# Option_key.net
KiCad netlist of a schematic drawn in Altium Designer
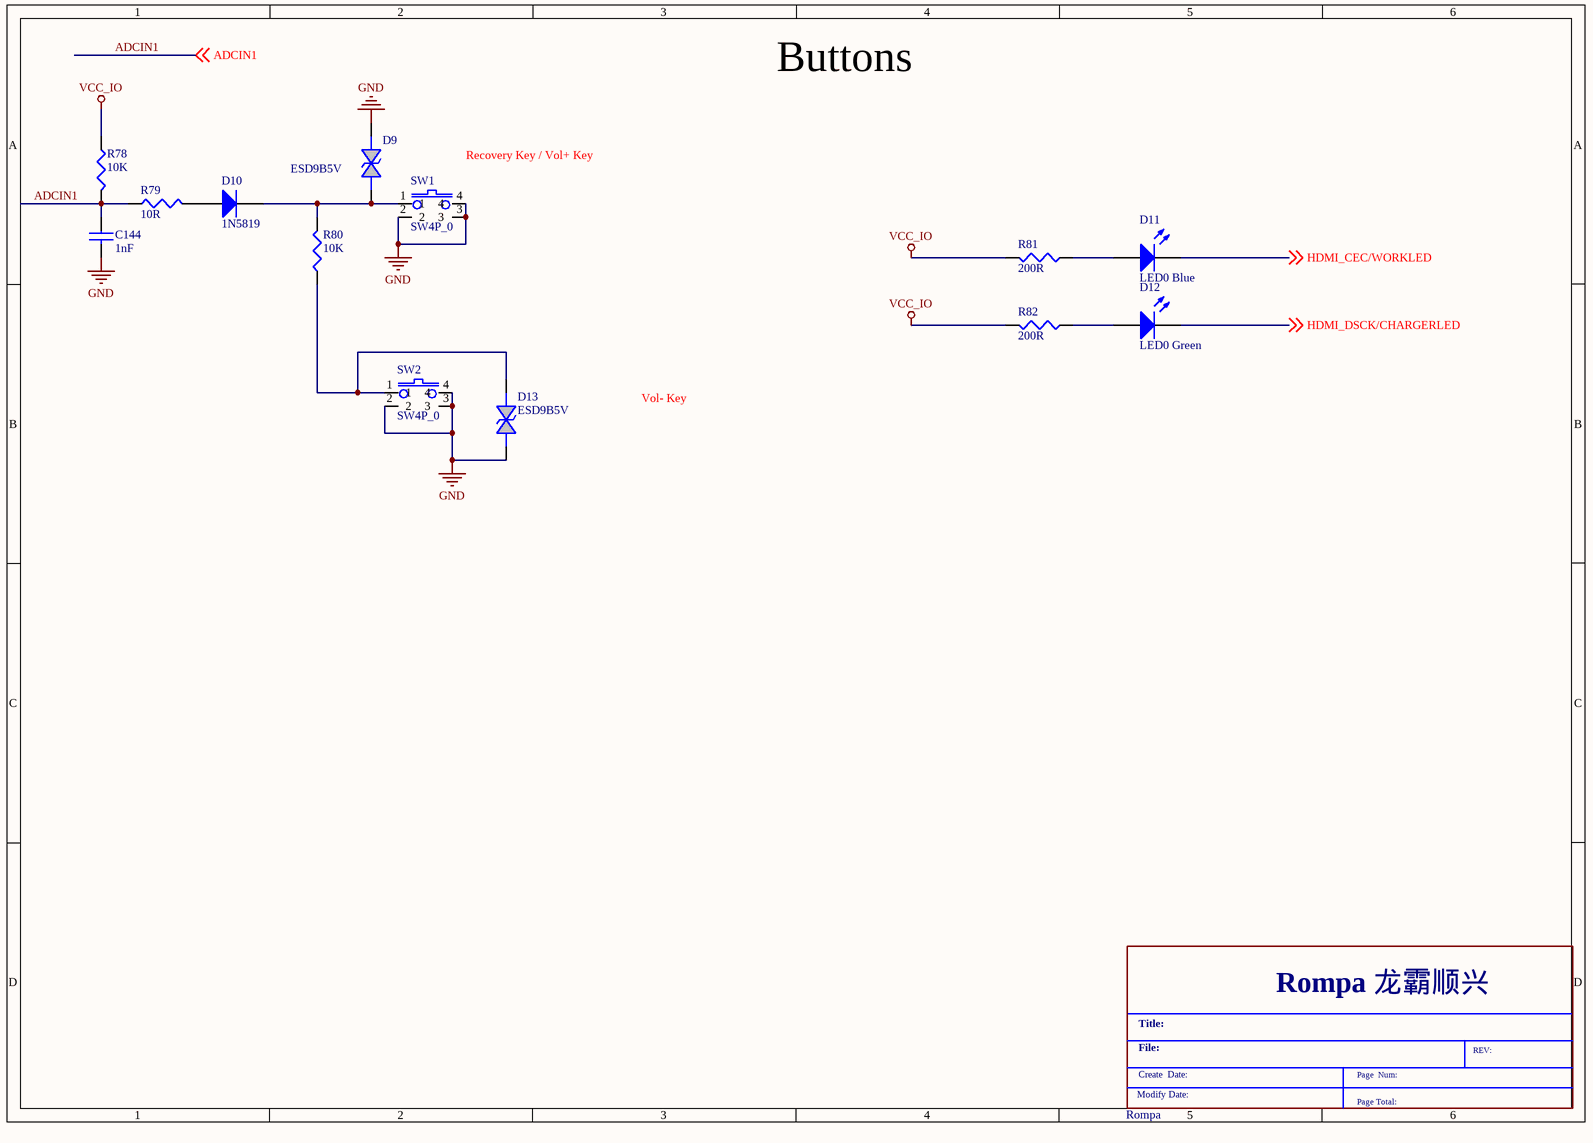
[diagram p0: Option_key.SchDoc]

(export (version "E")
  (design (tool "Eeschema 10.0.6"))
  (components
    (comp (ref "C144")
      (value "1nF")
      (footprint "C0402")
      (description "16V")
      (libsource (lib "RK3128_BETA_V03_20151231_Library") (part "CAP NP"))
    )
    (comp (ref "D9")
      (value "ESD9B5V")
      (description "FP:E0402N")
      (libsource (lib "RK3128_BETA_V03_20151231_Library") (part "DIODE BI-DIR TRIG"))
    )
    (comp (ref "D10")
      (value "1N5819")
      (fields (field (name "PUBLISHER") "Altium Limited"))
      (libsource (lib "Miscellaneous Devices") (part "Diode"))
    )
    (comp (ref "D11")
      (value "LED0 Blue")
      (footprint "1608[0603]")
      (description "Typical INFRARED GaAs LED   Blue")
      (fields (field (name "PUBLISHER") "Altium Limited"))
      (libsource (lib "Miscellaneous Devices") (part "LED0"))
    )
    (comp (ref "D12")
      (value "LED0 Green")
      (footprint "1608[0603]")
      (description "Typical INFRARED GaAs LED   Blue")
      (fields (field (name "PUBLISHER") "Altium Limited"))
      (libsource (lib "Miscellaneous Devices") (part "LED0"))
    )
    (comp (ref "D13")
      (value "ESD9B5V")
      (description "FP:E0402N")
      (libsource (lib "RK3128_BETA_V03_20151231_Library") (part "DIODE BI-DIR TRIG"))
    )
    (comp (ref "R78")
      (value "10K")
      (footprint "R0402")
      (description "%1")
      (libsource (lib "RK3128_BETA_V03_20151231_Library") (part "RESISTOR"))
    )
    (comp (ref "R79")
      (value "10R")
      (footprint "R0402")
      (libsource (lib "RK3128_BETA_V03_20151231_Library") (part "RESISTOR"))
    )
    (comp (ref "R80")
      (value "10K")
      (footprint "R0402")
      (libsource (lib "RK3128_BETA_V03_20151231_Library") (part "RESISTOR"))
    )
    (comp (ref "R81")
      (value "200R")
      (footprint "R0402")
      (libsource (lib "RK3128_BETA_V03_20151231_Library") (part "RESISTOR"))
    )
    (comp (ref "R82")
      (value "200R")
      (footprint "R0402")
      (libsource (lib "RK3128_BETA_V03_20151231_Library") (part "RESISTOR"))
    )
    (comp (ref "SW1") (value "SW4P_0") (libsource (lib "RK3128_BETA_V03_20151231_Library") (part "SW4P_0")))
    (comp (ref "SW2") (value "SW4P_0") (libsource (lib "RK3128_BETA_V03_20151231_Library") (part "SW4P_0")))
  )
  (nets
    (net (code "1") (name "ADCIN1") (class "Default")
      (node (ref "C144") (pin "1") (pinfunction "1_1") (pintype "passive"))
      (node (ref "R78") (pin "2") (pinfunction "2_2") (pintype "passive"))
      (node (ref "R79") (pin "1") (pinfunction "1_1") (pintype "passive"))
    )
    (net (code "2") (name "GND") (class "Default")
      (node (ref "C144") (pin "2") (pinfunction "2_2") (pintype "passive"))
      (node (ref "D13") (pin "2") (pinfunction "2_2") (pintype "passive"))
      (node (ref "D9") (pin "2") (pinfunction "2_2") (pintype "passive"))
      (node (ref "SW1") (pin "2") (pinfunction "2_2") (pintype "passive"))
      (node (ref "SW1") (pin "3") (pinfunction "3_3") (pintype "passive"))
      (node (ref "SW1") (pin "4") (pinfunction "4_4") (pintype "passive"))
      (node (ref "SW2") (pin "2") (pinfunction "2_2") (pintype "passive"))
      (node (ref "SW2") (pin "3") (pinfunction "3_3") (pintype "passive"))
      (node (ref "SW2") (pin "4") (pinfunction "4_4") (pintype "passive"))
    )
    (net (code "3") (name "HDMI_CEC{slash}WORKLED") (class "Default")
      (node (ref "D11") (pin "2") (pinfunction "K_2") (pintype "passive"))
    )
    (net (code "4") (name "HDMI_DSCK{slash}CHARGERLED") (class "Default")
      (node (ref "D12") (pin "2") (pinfunction "K_2") (pintype "passive"))
    )
    (net (code "5") (name "Net-(D10-A)") (class "Default")
      (node (ref "D10") (pin "1") (pinfunction "A_1") (pintype "passive"))
      (node (ref "R79") (pin "2") (pinfunction "2_2") (pintype "passive"))
    )
    (net (code "6") (name "Net-(D10-K)") (class "Default")
      (node (ref "D10") (pin "2") (pinfunction "K_2") (pintype "passive"))
      (node (ref "D9") (pin "1") (pinfunction "1_1") (pintype "passive"))
      (node (ref "R80") (pin "2") (pinfunction "2_2") (pintype "passive"))
      (node (ref "SW1") (pin "1") (pinfunction "1_1") (pintype "passive"))
    )
    (net (code "7") (name "Net-(D11-A)") (class "Default")
      (node (ref "D11") (pin "1") (pinfunction "A_1") (pintype "passive"))
      (node (ref "R81") (pin "1") (pinfunction "1_1") (pintype "passive"))
    )
    (net (code "8") (name "Net-(D12-A)") (class "Default")
      (node (ref "D12") (pin "1") (pinfunction "A_1") (pintype "passive"))
      (node (ref "R82") (pin "1") (pinfunction "1_1") (pintype "passive"))
    )
    (net (code "9") (name "Net-(D13-Pad1)") (class "Default")
      (node (ref "D13") (pin "1") (pinfunction "1_1") (pintype "passive"))
      (node (ref "R80") (pin "1") (pinfunction "1_1") (pintype "passive"))
      (node (ref "SW2") (pin "1") (pinfunction "1_1") (pintype "passive"))
    )
    (net (code "10") (name "VCC_IO") (class "Default")
      (node (ref "R78") (pin "1") (pinfunction "1_1") (pintype "passive"))
      (node (ref "R81") (pin "2") (pinfunction "2_2") (pintype "passive"))
      (node (ref "R82") (pin "2") (pinfunction "2_2") (pintype "passive"))
    )
  )
)
